# mainBoard.net
KiCad netlist of a schematic drawn in Altium Designer
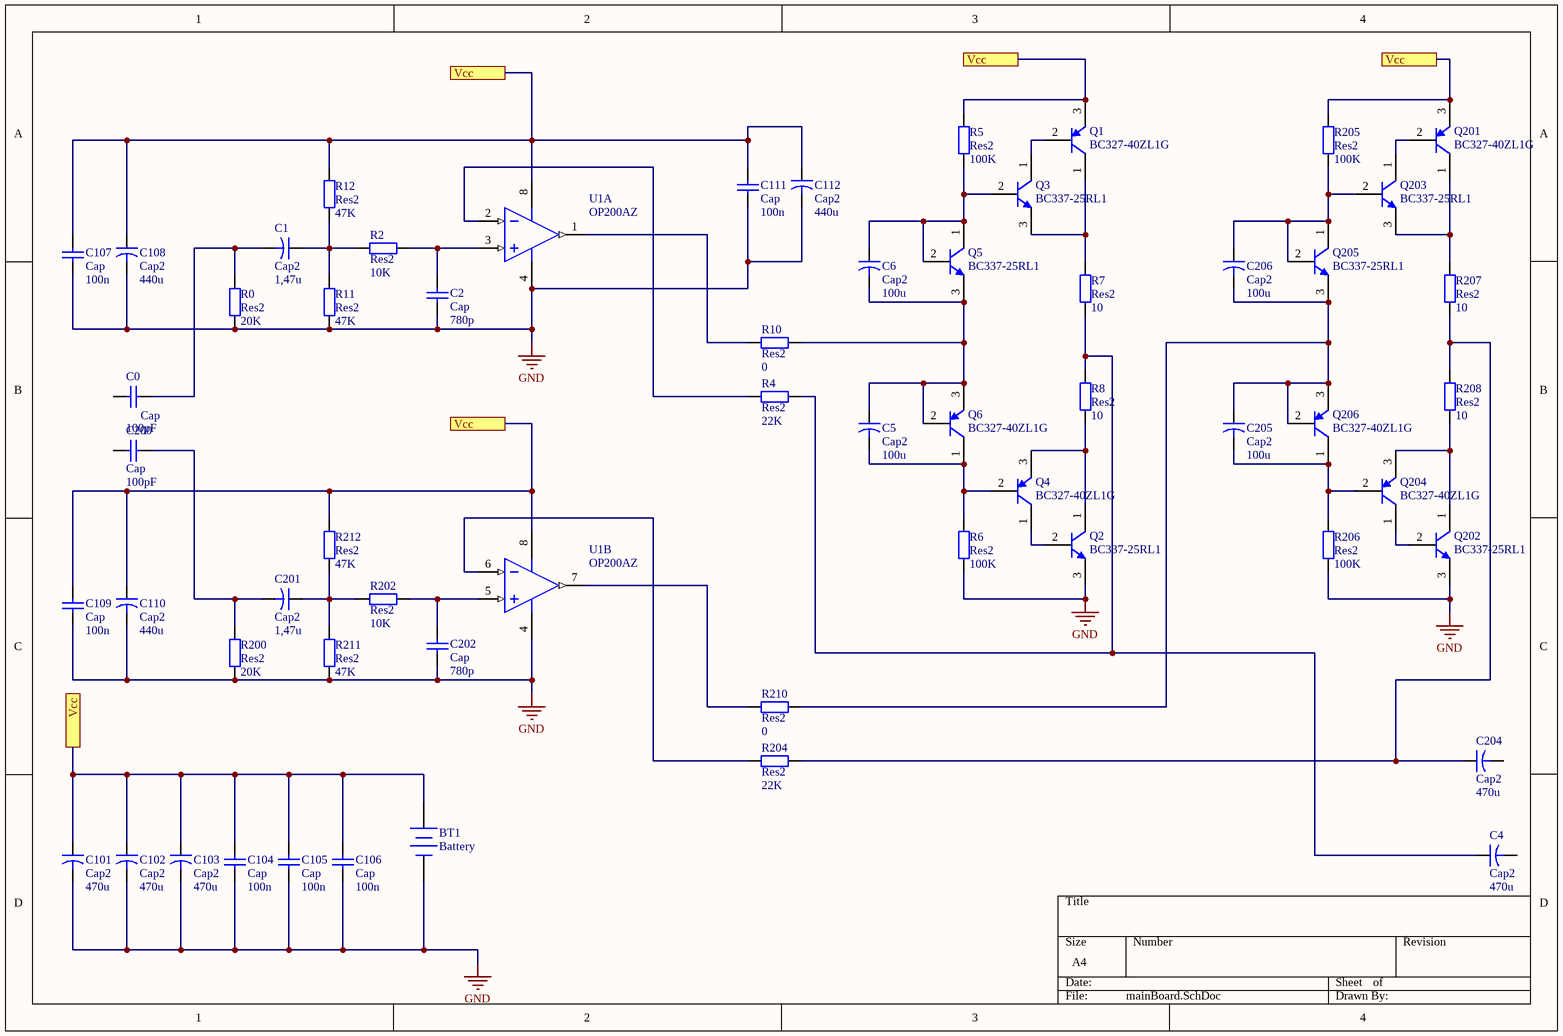
[diagram p0: mainBoard.SchDoc]

(export (version "E")
  (design (tool "Eeschema 10.0.6"))
  (components
    (comp (ref "BT1")
      (value "Battery")
      (footprint "BAT-2")
      (description "Multicell Battery")
      (fields (field (name "PUBLISHER") "Altium Limited"))
      (libsource (lib "Miscellaneous Devices") (part "Battery"))
    )
    (comp (ref "C0")
      (value "Cap")
      (footprint "RAD-0.3")
      (description "Capacitor")
      (fields (field (name "ALTIUM_VALUE") "100pF") (field (name "PUBLISHER") "Altium Limited"))
      (libsource (lib "Miscellaneous Devices") (part "Cap"))
    )
    (comp (ref "C1")
      (value "Cap2")
      (footprint "CAPR5-4X5")
      (description "Capacitor")
      (fields (field (name "ALTIUM_VALUE") "1,47u") (field (name "PUBLISHER") "Altium Limited"))
      (libsource (lib "Miscellaneous Devices") (part "Cap2"))
    )
    (comp (ref "C2")
      (value "Cap")
      (footprint "RAD-0.3")
      (description "Capacitor")
      (fields (field (name "ALTIUM_VALUE") "780p") (field (name "PUBLISHER") "Altium Limited"))
      (libsource (lib "Miscellaneous Devices") (part "Cap"))
    )
    (comp (ref "C4")
      (value "Cap2")
      (footprint "CAPR5-4X5")
      (description "Capacitor")
      (fields (field (name "ALTIUM_VALUE") "470u") (field (name "PUBLISHER") "Altium Limited"))
      (libsource (lib "Miscellaneous Devices") (part "Cap2"))
    )
    (comp (ref "C5")
      (value "Cap2")
      (footprint "CAPR5-4X5")
      (description "Capacitor")
      (fields (field (name "ALTIUM_VALUE") "100u") (field (name "PUBLISHER") "Altium Limited"))
      (libsource (lib "Miscellaneous Devices") (part "Cap2"))
    )
    (comp (ref "C6")
      (value "Cap2")
      (footprint "CAPR5-4X5")
      (description "Capacitor")
      (fields (field (name "ALTIUM_VALUE") "100u") (field (name "PUBLISHER") "Altium Limited"))
      (libsource (lib "Miscellaneous Devices") (part "Cap2"))
    )
    (comp (ref "C101")
      (value "Cap2")
      (footprint "CAPR5-4X5")
      (description "Capacitor")
      (fields (field (name "ALTIUM_VALUE") "470u") (field (name "PUBLISHER") "Altium Limited"))
      (libsource (lib "Miscellaneous Devices") (part "Cap2"))
    )
    (comp (ref "C102")
      (value "Cap2")
      (footprint "CAPR5-4X5")
      (description "Capacitor")
      (fields (field (name "ALTIUM_VALUE") "470u") (field (name "PUBLISHER") "Altium Limited"))
      (libsource (lib "Miscellaneous Devices") (part "Cap2"))
    )
    (comp (ref "C103")
      (value "Cap2")
      (footprint "CAPR5-4X5")
      (description "Capacitor")
      (fields (field (name "ALTIUM_VALUE") "470u") (field (name "PUBLISHER") "Altium Limited"))
      (libsource (lib "Miscellaneous Devices") (part "Cap2"))
    )
    (comp (ref "C104")
      (value "Cap")
      (footprint "RAD-0.3")
      (description "Capacitor")
      (fields (field (name "ALTIUM_VALUE") "100n") (field (name "PUBLISHER") "Altium Limited"))
      (libsource (lib "Miscellaneous Devices") (part "Cap"))
    )
    (comp (ref "C105")
      (value "Cap")
      (footprint "RAD-0.3")
      (description "Capacitor")
      (fields (field (name "ALTIUM_VALUE") "100n") (field (name "PUBLISHER") "Altium Limited"))
      (libsource (lib "Miscellaneous Devices") (part "Cap"))
    )
    (comp (ref "C106")
      (value "Cap")
      (footprint "RAD-0.3")
      (description "Capacitor")
      (fields (field (name "ALTIUM_VALUE") "100n") (field (name "PUBLISHER") "Altium Limited"))
      (libsource (lib "Miscellaneous Devices") (part "Cap"))
    )
    (comp (ref "C107")
      (value "Cap")
      (footprint "RAD-0.3")
      (description "Capacitor")
      (fields (field (name "ALTIUM_VALUE") "100n") (field (name "PUBLISHER") "Altium Limited"))
      (libsource (lib "Miscellaneous Devices") (part "Cap"))
    )
    (comp (ref "C108")
      (value "Cap2")
      (footprint "CAPR5-4X5")
      (description "Capacitor")
      (fields (field (name "ALTIUM_VALUE") "440u") (field (name "PUBLISHER") "Altium Limited"))
      (libsource (lib "Miscellaneous Devices") (part "Cap2"))
    )
    (comp (ref "C109")
      (value "Cap")
      (footprint "RAD-0.3")
      (description "Capacitor")
      (fields (field (name "ALTIUM_VALUE") "100n") (field (name "PUBLISHER") "Altium Limited"))
      (libsource (lib "Miscellaneous Devices") (part "Cap"))
    )
    (comp (ref "C110")
      (value "Cap2")
      (footprint "CAPR5-4X5")
      (description "Capacitor")
      (fields (field (name "ALTIUM_VALUE") "440u") (field (name "PUBLISHER") "Altium Limited"))
      (libsource (lib "Miscellaneous Devices") (part "Cap2"))
    )
    (comp (ref "C111")
      (value "Cap")
      (footprint "RAD-0.3")
      (description "Capacitor")
      (fields (field (name "ALTIUM_VALUE") "100n") (field (name "PUBLISHER") "Altium Limited"))
      (libsource (lib "Miscellaneous Devices") (part "Cap"))
    )
    (comp (ref "C112")
      (value "Cap2")
      (footprint "CAPR5-4X5")
      (description "Capacitor")
      (fields (field (name "ALTIUM_VALUE") "440u") (field (name "PUBLISHER") "Altium Limited"))
      (libsource (lib "Miscellaneous Devices") (part "Cap2"))
    )
    (comp (ref "C200")
      (value "Cap")
      (footprint "RAD-0.3")
      (description "Capacitor")
      (fields (field (name "ALTIUM_VALUE") "100pF") (field (name "PUBLISHER") "Altium Limited"))
      (libsource (lib "Miscellaneous Devices") (part "Cap"))
    )
    (comp (ref "C201")
      (value "Cap2")
      (footprint "CAPR5-4X5")
      (description "Capacitor")
      (fields (field (name "ALTIUM_VALUE") "1,47u") (field (name "PUBLISHER") "Altium Limited"))
      (libsource (lib "Miscellaneous Devices") (part "Cap2"))
    )
    (comp (ref "C202")
      (value "Cap")
      (footprint "RAD-0.3")
      (description "Capacitor")
      (fields (field (name "ALTIUM_VALUE") "780p") (field (name "PUBLISHER") "Altium Limited"))
      (libsource (lib "Miscellaneous Devices") (part "Cap"))
    )
    (comp (ref "C204")
      (value "Cap2")
      (footprint "CAPR5-4X5")
      (description "Capacitor")
      (fields (field (name "ALTIUM_VALUE") "470u") (field (name "PUBLISHER") "Altium Limited"))
      (libsource (lib "Miscellaneous Devices") (part "Cap2"))
    )
    (comp (ref "C205")
      (value "Cap2")
      (footprint "CAPR5-4X5")
      (description "Capacitor")
      (fields (field (name "ALTIUM_VALUE") "100u") (field (name "PUBLISHER") "Altium Limited"))
      (libsource (lib "Miscellaneous Devices") (part "Cap2"))
    )
    (comp (ref "C206")
      (value "Cap2")
      (footprint "CAPR5-4X5")
      (description "Capacitor")
      (fields (field (name "ALTIUM_VALUE") "100u") (field (name "PUBLISHER") "Altium Limited"))
      (libsource (lib "Miscellaneous Devices") (part "Cap2"))
    )
    (comp (ref "Q1")
      (value "BC327-40ZL1G")
      (footprint "ONSC-TO-92-3-29-11_AM_BL")
      (description "Amplifier Transistor, PNP Silicon, 3-Pin TO-92, Pb-Free, Ammo Box")
      (fields (field (name "MANUFACTURER") "On Semiconductor"))
      (libsource (lib "ON Semi General Purpose Transistors") (part "BC327-40ZL1G"))
    )
    (comp (ref "Q2")
      (value "BC337-25RL1")
      (footprint "ONSC-TO-92-3-29-11_AM_BL")
      (description "Amplifier Transistor, NPN Silicon, 3-Pin TO-92, Tape and Reel")
      (fields (field (name "MANUFACTURER") "On Semiconductor"))
      (libsource (lib "ON Semi General Purpose Transistors") (part "BC337-25RL1"))
    )
    (comp (ref "Q3")
      (value "BC337-25RL1")
      (footprint "ONSC-TO-92-3-29-11_AM_BL")
      (description "Amplifier Transistor, NPN Silicon, 3-Pin TO-92, Tape and Reel")
      (fields (field (name "MANUFACTURER") "On Semiconductor"))
      (libsource (lib "ON Semi General Purpose Transistors") (part "BC337-25RL1"))
    )
    (comp (ref "Q4")
      (value "BC327-40ZL1G")
      (footprint "ONSC-TO-92-3-29-11_AM_BL")
      (description "Amplifier Transistor, PNP Silicon, 3-Pin TO-92, Pb-Free, Ammo Box")
      (fields (field (name "MANUFACTURER") "On Semiconductor"))
      (libsource (lib "ON Semi General Purpose Transistors") (part "BC327-40ZL1G"))
    )
    (comp (ref "Q5")
      (value "BC337-25RL1")
      (footprint "ONSC-TO-92-3-29-11_AM_BL")
      (description "Amplifier Transistor, NPN Silicon, 3-Pin TO-92, Tape and Reel")
      (fields (field (name "MANUFACTURER") "On Semiconductor"))
      (libsource (lib "ON Semi General Purpose Transistors") (part "BC337-25RL1"))
    )
    (comp (ref "Q6")
      (value "BC327-40ZL1G")
      (footprint "ONSC-TO-92-3-29-11_AM_BL")
      (description "Amplifier Transistor, PNP Silicon, 3-Pin TO-92, Pb-Free, Ammo Box")
      (fields (field (name "MANUFACTURER") "On Semiconductor"))
      (libsource (lib "ON Semi General Purpose Transistors") (part "BC327-40ZL1G"))
    )
    (comp (ref "Q201")
      (value "BC327-40ZL1G")
      (footprint "ONSC-TO-92-3-29-11_AM_BL")
      (description "Amplifier Transistor, PNP Silicon, 3-Pin TO-92, Pb-Free, Ammo Box")
      (fields (field (name "MANUFACTURER") "On Semiconductor"))
      (libsource (lib "ON Semi General Purpose Transistors") (part "BC327-40ZL1G"))
    )
    (comp (ref "Q202")
      (value "BC337-25RL1")
      (footprint "ONSC-TO-92-3-29-11_AM_BL")
      (description "Amplifier Transistor, NPN Silicon, 3-Pin TO-92, Tape and Reel")
      (fields (field (name "MANUFACTURER") "On Semiconductor"))
      (libsource (lib "ON Semi General Purpose Transistors") (part "BC337-25RL1"))
    )
    (comp (ref "Q203")
      (value "BC337-25RL1")
      (footprint "ONSC-TO-92-3-29-11_AM_BL")
      (description "Amplifier Transistor, NPN Silicon, 3-Pin TO-92, Tape and Reel")
      (fields (field (name "MANUFACTURER") "On Semiconductor"))
      (libsource (lib "ON Semi General Purpose Transistors") (part "BC337-25RL1"))
    )
    (comp (ref "Q204")
      (value "BC327-40ZL1G")
      (footprint "ONSC-TO-92-3-29-11_AM_BL")
      (description "Amplifier Transistor, PNP Silicon, 3-Pin TO-92, Pb-Free, Ammo Box")
      (fields (field (name "MANUFACTURER") "On Semiconductor"))
      (libsource (lib "ON Semi General Purpose Transistors") (part "BC327-40ZL1G"))
    )
    (comp (ref "Q205")
      (value "BC337-25RL1")
      (footprint "ONSC-TO-92-3-29-11_AM_BL")
      (description "Amplifier Transistor, NPN Silicon, 3-Pin TO-92, Tape and Reel")
      (fields (field (name "MANUFACTURER") "On Semiconductor"))
      (libsource (lib "ON Semi General Purpose Transistors") (part "BC337-25RL1"))
    )
    (comp (ref "Q206")
      (value "BC327-40ZL1G")
      (footprint "ONSC-TO-92-3-29-11_AM_BL")
      (description "Amplifier Transistor, PNP Silicon, 3-Pin TO-92, Pb-Free, Ammo Box")
      (fields (field (name "MANUFACTURER") "On Semiconductor"))
      (libsource (lib "ON Semi General Purpose Transistors") (part "BC327-40ZL1G"))
    )
    (comp (ref "R0")
      (value "Res2")
      (footprint "AXIAL-0.4")
      (description "Resistor")
      (fields (field (name "ALTIUM_VALUE") "20K") (field (name "PUBLISHER") "Altium Limited"))
      (libsource (lib "Miscellaneous Devices") (part "Res2"))
    )
    (comp (ref "R2")
      (value "Res2")
      (footprint "AXIAL-0.4")
      (description "Resistor")
      (fields (field (name "ALTIUM_VALUE") "10K") (field (name "PUBLISHER") "Altium Limited"))
      (libsource (lib "") (part "Res2_1"))
    )
    (comp (ref "R4")
      (value "Res2")
      (footprint "AXIAL-0.4")
      (description "Resistor")
      (fields (field (name "ALTIUM_VALUE") "22K") (field (name "PUBLISHER") "Altium Limited"))
      (libsource (lib "") (part "Res2_1"))
    )
    (comp (ref "R5")
      (value "Res2")
      (footprint "AXIAL-0.4")
      (description "Resistor")
      (fields (field (name "ALTIUM_VALUE") "100K") (field (name "PUBLISHER") "Altium Limited"))
      (libsource (lib "Miscellaneous Devices") (part "Res2"))
    )
    (comp (ref "R6")
      (value "Res2")
      (footprint "AXIAL-0.4")
      (description "Resistor")
      (fields (field (name "ALTIUM_VALUE") "100K") (field (name "PUBLISHER") "Altium Limited"))
      (libsource (lib "Miscellaneous Devices") (part "Res2"))
    )
    (comp (ref "R7")
      (value "Res2")
      (footprint "AXIAL-0.4")
      (description "Resistor")
      (fields (field (name "ALTIUM_VALUE") "10") (field (name "PUBLISHER") "Altium Limited"))
      (libsource (lib "Miscellaneous Devices") (part "Res2"))
    )
    (comp (ref "R8")
      (value "Res2")
      (footprint "AXIAL-0.4")
      (description "Resistor")
      (fields (field (name "ALTIUM_VALUE") "10") (field (name "PUBLISHER") "Altium Limited"))
      (libsource (lib "Miscellaneous Devices") (part "Res2"))
    )
    (comp (ref "R10")
      (value "Res2")
      (footprint "AXIAL-0.4")
      (description "Resistor")
      (fields (field (name "ALTIUM_VALUE") "0") (field (name "PUBLISHER") "Altium Limited"))
      (libsource (lib "") (part "Res2_1"))
    )
    (comp (ref "R11")
      (value "Res2")
      (footprint "AXIAL-0.4")
      (description "Resistor")
      (fields (field (name "ALTIUM_VALUE") "47K") (field (name "PUBLISHER") "Altium Limited"))
      (libsource (lib "Miscellaneous Devices") (part "Res2"))
    )
    (comp (ref "R12")
      (value "Res2")
      (footprint "AXIAL-0.4")
      (description "Resistor")
      (fields (field (name "ALTIUM_VALUE") "47K") (field (name "PUBLISHER") "Altium Limited"))
      (libsource (lib "Miscellaneous Devices") (part "Res2"))
    )
    (comp (ref "R200")
      (value "Res2")
      (footprint "AXIAL-0.4")
      (description "Resistor")
      (fields (field (name "ALTIUM_VALUE") "20K") (field (name "PUBLISHER") "Altium Limited"))
      (libsource (lib "Miscellaneous Devices") (part "Res2"))
    )
    (comp (ref "R202")
      (value "Res2")
      (footprint "AXIAL-0.4")
      (description "Resistor")
      (fields (field (name "ALTIUM_VALUE") "10K") (field (name "PUBLISHER") "Altium Limited"))
      (libsource (lib "") (part "Res2_1"))
    )
    (comp (ref "R204")
      (value "Res2")
      (footprint "AXIAL-0.4")
      (description "Resistor")
      (fields (field (name "ALTIUM_VALUE") "22K") (field (name "PUBLISHER") "Altium Limited"))
      (libsource (lib "") (part "Res2_1"))
    )
    (comp (ref "R205")
      (value "Res2")
      (footprint "AXIAL-0.4")
      (description "Resistor")
      (fields (field (name "ALTIUM_VALUE") "100K") (field (name "PUBLISHER") "Altium Limited"))
      (libsource (lib "Miscellaneous Devices") (part "Res2"))
    )
    (comp (ref "R206")
      (value "Res2")
      (footprint "AXIAL-0.4")
      (description "Resistor")
      (fields (field (name "ALTIUM_VALUE") "100K") (field (name "PUBLISHER") "Altium Limited"))
      (libsource (lib "Miscellaneous Devices") (part "Res2"))
    )
    (comp (ref "R207")
      (value "Res2")
      (footprint "AXIAL-0.4")
      (description "Resistor")
      (fields (field (name "ALTIUM_VALUE") "10") (field (name "PUBLISHER") "Altium Limited"))
      (libsource (lib "Miscellaneous Devices") (part "Res2"))
    )
    (comp (ref "R208")
      (value "Res2")
      (footprint "AXIAL-0.4")
      (description "Resistor")
      (fields (field (name "ALTIUM_VALUE") "10") (field (name "PUBLISHER") "Altium Limited"))
      (libsource (lib "Miscellaneous Devices") (part "Res2"))
    )
    (comp (ref "R210")
      (value "Res2")
      (footprint "AXIAL-0.4")
      (description "Resistor")
      (fields (field (name "ALTIUM_VALUE") "0") (field (name "PUBLISHER") "Altium Limited"))
      (libsource (lib "") (part "Res2_1"))
    )
    (comp (ref "R211")
      (value "Res2")
      (footprint "AXIAL-0.4")
      (description "Resistor")
      (fields (field (name "ALTIUM_VALUE") "47K") (field (name "PUBLISHER") "Altium Limited"))
      (libsource (lib "Miscellaneous Devices") (part "Res2"))
    )
    (comp (ref "R212")
      (value "Res2")
      (footprint "AXIAL-0.4")
      (description "Resistor")
      (fields (field (name "ALTIUM_VALUE") "47K") (field (name "PUBLISHER") "Altium Limited"))
      (libsource (lib "Miscellaneous Devices") (part "Res2"))
    )
    (comp (ref "U1")
      (value "OP200AZ")
      (footprint "ADI-Q-8")
      (fields (field (name "GENERIC PART NUMBER") "OP200") (field (name "MANUFACTURER") "Analog Devices"))
      (libsource (lib "Analog Devices Operational Amplifiers") (part "OP200AZ"))
    )
  )
  (nets
    (net (code "1") (name "/Vcc") (class "Default")
      (node (ref "BT1") (pin "1") (pinfunction "+_1") (pintype "passive"))
      (node (ref "C101") (pin "1") (pinfunction "1_1") (pintype "passive"))
      (node (ref "C102") (pin "1") (pinfunction "1_1") (pintype "passive"))
      (node (ref "C103") (pin "1") (pinfunction "1_1") (pintype "passive"))
      (node (ref "C104") (pin "2") (pinfunction "2_2") (pintype "passive"))
      (node (ref "C105") (pin "2") (pinfunction "2_2") (pintype "passive"))
      (node (ref "C106") (pin "2") (pinfunction "2_2") (pintype "passive"))
      (node (ref "C107") (pin "2") (pinfunction "2_2") (pintype "passive"))
      (node (ref "C108") (pin "1") (pinfunction "1_1") (pintype "passive"))
      (node (ref "C109") (pin "2") (pinfunction "2_2") (pintype "passive"))
      (node (ref "C110") (pin "1") (pinfunction "1_1") (pintype "passive"))
      (node (ref "C111") (pin "2") (pinfunction "2_2") (pintype "passive"))
      (node (ref "C112") (pin "1") (pinfunction "1_1") (pintype "passive"))
      (node (ref "Q1") (pin "3") (pinfunction "E_3") (pintype "passive"))
      (node (ref "Q201") (pin "3") (pinfunction "E_3") (pintype "passive"))
      (node (ref "R12") (pin "2") (pinfunction "2_2") (pintype "passive"))
      (node (ref "R205") (pin "2") (pinfunction "2_2") (pintype "passive"))
      (node (ref "R212") (pin "2") (pinfunction "2_2") (pintype "passive"))
      (node (ref "R5") (pin "2") (pinfunction "2_2") (pintype "passive"))
      (node (ref "U1") (pin "8") (pinfunction "+V_8") (pintype "power_in"))
    )
    (net (code "2") (name "GND") (class "Default")
      (node (ref "BT1") (pin "2") (pinfunction "-_2") (pintype "passive"))
      (node (ref "C101") (pin "2") (pinfunction "2_2") (pintype "passive"))
      (node (ref "C102") (pin "2") (pinfunction "2_2") (pintype "passive"))
      (node (ref "C103") (pin "2") (pinfunction "2_2") (pintype "passive"))
      (node (ref "C104") (pin "1") (pinfunction "1_1") (pintype "passive"))
      (node (ref "C105") (pin "1") (pinfunction "1_1") (pintype "passive"))
      (node (ref "C106") (pin "1") (pinfunction "1_1") (pintype "passive"))
      (node (ref "C107") (pin "1") (pinfunction "1_1") (pintype "passive"))
      (node (ref "C108") (pin "2") (pinfunction "2_2") (pintype "passive"))
      (node (ref "C109") (pin "1") (pinfunction "1_1") (pintype "passive"))
      (node (ref "C110") (pin "2") (pinfunction "2_2") (pintype "passive"))
      (node (ref "C111") (pin "1") (pinfunction "1_1") (pintype "passive"))
      (node (ref "C112") (pin "2") (pinfunction "2_2") (pintype "passive"))
      (node (ref "C2") (pin "1") (pinfunction "1_1") (pintype "passive"))
      (node (ref "C202") (pin "1") (pinfunction "1_1") (pintype "passive"))
      (node (ref "Q2") (pin "3") (pinfunction "E_3") (pintype "passive"))
      (node (ref "Q202") (pin "3") (pinfunction "E_3") (pintype "passive"))
      (node (ref "R0") (pin "1") (pinfunction "1_1") (pintype "passive"))
      (node (ref "R11") (pin "1") (pinfunction "1_1") (pintype "passive"))
      (node (ref "R200") (pin "1") (pinfunction "1_1") (pintype "passive"))
      (node (ref "R206") (pin "1") (pinfunction "1_1") (pintype "passive"))
      (node (ref "R211") (pin "1") (pinfunction "1_1") (pintype "passive"))
      (node (ref "R6") (pin "1") (pinfunction "1_1") (pintype "passive"))
      (node (ref "U1") (pin "4") (pinfunction "-V_4") (pintype "power_in"))
    )
    (net (code "3") (name "Net-(C0-Pad1)") (class "Default")
      (node (ref "C0") (pin "1") (pinfunction "1_1") (pintype "passive"))
      (node (ref "C1") (pin "2") (pinfunction "2_2") (pintype "passive"))
      (node (ref "R0") (pin "2") (pinfunction "2_2") (pintype "passive"))
    )
    (net (code "4") (name "Net-(C1-Pad1)") (class "Default")
      (node (ref "C1") (pin "1") (pinfunction "1_1") (pintype "passive"))
      (node (ref "R11") (pin "2") (pinfunction "2_2") (pintype "passive"))
      (node (ref "R12") (pin "1") (pinfunction "1_1") (pintype "passive"))
      (node (ref "R2") (pin "2") (pinfunction "2_2") (pintype "passive"))
    )
    (net (code "5") (name "Net-(C4-Pad1)") (class "Default")
      (node (ref "C4") (pin "1") (pinfunction "1_1") (pintype "passive"))
      (node (ref "R4") (pin "1") (pinfunction "1_1") (pintype "passive"))
      (node (ref "R7") (pin "1") (pinfunction "1_1") (pintype "passive"))
      (node (ref "R8") (pin "2") (pinfunction "2_2") (pintype "passive"))
    )
    (net (code "6") (name "Net-(C200-Pad1)") (class "Default")
      (node (ref "C200") (pin "1") (pinfunction "1_1") (pintype "passive"))
      (node (ref "C201") (pin "2") (pinfunction "2_2") (pintype "passive"))
      (node (ref "R200") (pin "2") (pinfunction "2_2") (pintype "passive"))
    )
    (net (code "7") (name "Net-(C201-Pad1)") (class "Default")
      (node (ref "C201") (pin "1") (pinfunction "1_1") (pintype "passive"))
      (node (ref "R202") (pin "2") (pinfunction "2_2") (pintype "passive"))
      (node (ref "R211") (pin "2") (pinfunction "2_2") (pintype "passive"))
      (node (ref "R212") (pin "1") (pinfunction "1_1") (pintype "passive"))
    )
    (net (code "8") (name "Net-(C204-Pad1)") (class "Default")
      (node (ref "C204") (pin "1") (pinfunction "1_1") (pintype "passive"))
      (node (ref "R204") (pin "1") (pinfunction "1_1") (pintype "passive"))
      (node (ref "R207") (pin "1") (pinfunction "1_1") (pintype "passive"))
      (node (ref "R208") (pin "2") (pinfunction "2_2") (pintype "passive"))
    )
    (net (code "9") (name "Net-(Q1-B)") (class "Default")
      (node (ref "Q1") (pin "2") (pinfunction "B_2") (pintype "passive"))
      (node (ref "Q3") (pin "1") (pinfunction "C_1") (pintype "passive"))
    )
    (net (code "10") (name "Net-(Q1-C)") (class "Default")
      (node (ref "Q1") (pin "1") (pinfunction "C_1") (pintype "passive"))
      (node (ref "Q3") (pin "3") (pinfunction "E_3") (pintype "passive"))
      (node (ref "R7") (pin "2") (pinfunction "2_2") (pintype "passive"))
    )
    (net (code "11") (name "Net-(Q2-B)") (class "Default")
      (node (ref "Q2") (pin "2") (pinfunction "B_2") (pintype "passive"))
      (node (ref "Q4") (pin "1") (pinfunction "C_1") (pintype "passive"))
    )
    (net (code "12") (name "Net-(Q2-C)") (class "Default")
      (node (ref "Q2") (pin "1") (pinfunction "C_1") (pintype "passive"))
      (node (ref "Q4") (pin "3") (pinfunction "E_3") (pintype "passive"))
      (node (ref "R8") (pin "1") (pinfunction "1_1") (pintype "passive"))
    )
    (net (code "13") (name "Net-(Q3-B)") (class "Default")
      (node (ref "C6") (pin "1") (pinfunction "1_1") (pintype "passive"))
      (node (ref "Q3") (pin "2") (pinfunction "B_2") (pintype "passive"))
      (node (ref "Q5") (pin "1") (pinfunction "C_1") (pintype "passive"))
      (node (ref "Q5") (pin "2") (pinfunction "B_2") (pintype "passive"))
      (node (ref "R5") (pin "1") (pinfunction "1_1") (pintype "passive"))
    )
    (net (code "14") (name "Net-(Q4-B)") (class "Default")
      (node (ref "C5") (pin "2") (pinfunction "2_2") (pintype "passive"))
      (node (ref "Q4") (pin "2") (pinfunction "B_2") (pintype "passive"))
      (node (ref "Q6") (pin "1") (pinfunction "C_1") (pintype "passive"))
      (node (ref "R6") (pin "2") (pinfunction "2_2") (pintype "passive"))
    )
    (net (code "15") (name "Net-(Q5-E)") (class "Default")
      (node (ref "C5") (pin "1") (pinfunction "1_1") (pintype "passive"))
      (node (ref "C6") (pin "2") (pinfunction "2_2") (pintype "passive"))
      (node (ref "Q5") (pin "3") (pinfunction "E_3") (pintype "passive"))
      (node (ref "Q6") (pin "2") (pinfunction "B_2") (pintype "passive"))
      (node (ref "Q6") (pin "3") (pinfunction "E_3") (pintype "passive"))
      (node (ref "R10") (pin "1") (pinfunction "1_1") (pintype "passive"))
    )
    (net (code "16") (name "Net-(Q201-B)") (class "Default")
      (node (ref "Q201") (pin "2") (pinfunction "B_2") (pintype "passive"))
      (node (ref "Q203") (pin "1") (pinfunction "C_1") (pintype "passive"))
    )
    (net (code "17") (name "Net-(Q201-C)") (class "Default")
      (node (ref "Q201") (pin "1") (pinfunction "C_1") (pintype "passive"))
      (node (ref "Q203") (pin "3") (pinfunction "E_3") (pintype "passive"))
      (node (ref "R207") (pin "2") (pinfunction "2_2") (pintype "passive"))
    )
    (net (code "18") (name "Net-(Q202-B)") (class "Default")
      (node (ref "Q202") (pin "2") (pinfunction "B_2") (pintype "passive"))
      (node (ref "Q204") (pin "1") (pinfunction "C_1") (pintype "passive"))
    )
    (net (code "19") (name "Net-(Q202-C)") (class "Default")
      (node (ref "Q202") (pin "1") (pinfunction "C_1") (pintype "passive"))
      (node (ref "Q204") (pin "3") (pinfunction "E_3") (pintype "passive"))
      (node (ref "R208") (pin "1") (pinfunction "1_1") (pintype "passive"))
    )
    (net (code "20") (name "Net-(Q203-B)") (class "Default")
      (node (ref "C206") (pin "1") (pinfunction "1_1") (pintype "passive"))
      (node (ref "Q203") (pin "2") (pinfunction "B_2") (pintype "passive"))
      (node (ref "Q205") (pin "1") (pinfunction "C_1") (pintype "passive"))
      (node (ref "Q205") (pin "2") (pinfunction "B_2") (pintype "passive"))
      (node (ref "R205") (pin "1") (pinfunction "1_1") (pintype "passive"))
    )
    (net (code "21") (name "Net-(Q204-B)") (class "Default")
      (node (ref "C205") (pin "2") (pinfunction "2_2") (pintype "passive"))
      (node (ref "Q204") (pin "2") (pinfunction "B_2") (pintype "passive"))
      (node (ref "Q206") (pin "1") (pinfunction "C_1") (pintype "passive"))
      (node (ref "R206") (pin "2") (pinfunction "2_2") (pintype "passive"))
    )
    (net (code "22") (name "Net-(Q205-E)") (class "Default")
      (node (ref "C205") (pin "1") (pinfunction "1_1") (pintype "passive"))
      (node (ref "C206") (pin "2") (pinfunction "2_2") (pintype "passive"))
      (node (ref "Q205") (pin "3") (pinfunction "E_3") (pintype "passive"))
      (node (ref "Q206") (pin "2") (pinfunction "B_2") (pintype "passive"))
      (node (ref "Q206") (pin "3") (pinfunction "E_3") (pintype "passive"))
      (node (ref "R210") (pin "1") (pinfunction "1_1") (pintype "passive"))
    )
    (net (code "23") (name "Net-(U1A-+IN_A)") (class "Default")
      (node (ref "C2") (pin "2") (pinfunction "2_2") (pintype "passive"))
      (node (ref "R2") (pin "1") (pinfunction "1_1") (pintype "passive"))
      (node (ref "U1") (pin "3") (pinfunction "+IN_A_3") (pintype "input"))
    )
    (net (code "24") (name "Net-(U1A--IN_A)") (class "Default")
      (node (ref "R4") (pin "2") (pinfunction "2_2") (pintype "passive"))
      (node (ref "U1") (pin "2") (pinfunction "-IN_A_2") (pintype "input"))
    )
    (net (code "25") (name "Net-(U1A-OUT_A)") (class "Default")
      (node (ref "R10") (pin "2") (pinfunction "2_2") (pintype "passive"))
      (node (ref "U1") (pin "1") (pinfunction "OUT_A_1") (pintype "output"))
    )
    (net (code "26") (name "Net-(U1B-+IN_B)") (class "Default")
      (node (ref "C202") (pin "2") (pinfunction "2_2") (pintype "passive"))
      (node (ref "R202") (pin "1") (pinfunction "1_1") (pintype "passive"))
      (node (ref "U1") (pin "5") (pinfunction "+IN_B_5") (pintype "input"))
    )
    (net (code "27") (name "Net-(U1B--IN_B)") (class "Default")
      (node (ref "R204") (pin "2") (pinfunction "2_2") (pintype "passive"))
      (node (ref "U1") (pin "6") (pinfunction "-IN_B_6") (pintype "input"))
    )
    (net (code "28") (name "Net-(U1B-OUT_B)") (class "Default")
      (node (ref "R210") (pin "2") (pinfunction "2_2") (pintype "passive"))
      (node (ref "U1") (pin "7") (pinfunction "OUT_B_7") (pintype "output"))
    )
    (net (code "29") (name "unconnected-(C0-Pad2)") (class "Default")
      (node (ref "C0") (pin "2") (pinfunction "2_2") (pintype "passive"))
    )
    (net (code "30") (name "unconnected-(C4-Pad2)") (class "Default")
      (node (ref "C4") (pin "2") (pinfunction "2_2") (pintype "passive"))
    )
    (net (code "31") (name "unconnected-(C200-Pad2)") (class "Default")
      (node (ref "C200") (pin "2") (pinfunction "2_2") (pintype "passive"))
    )
    (net (code "32") (name "unconnected-(C204-Pad2)") (class "Default")
      (node (ref "C204") (pin "2") (pinfunction "2_2") (pintype "passive"))
    )
  )
)
